# SmartDriveTestStand_SingleCape.net
KiCad netlist of a schematic drawn in EAGLE
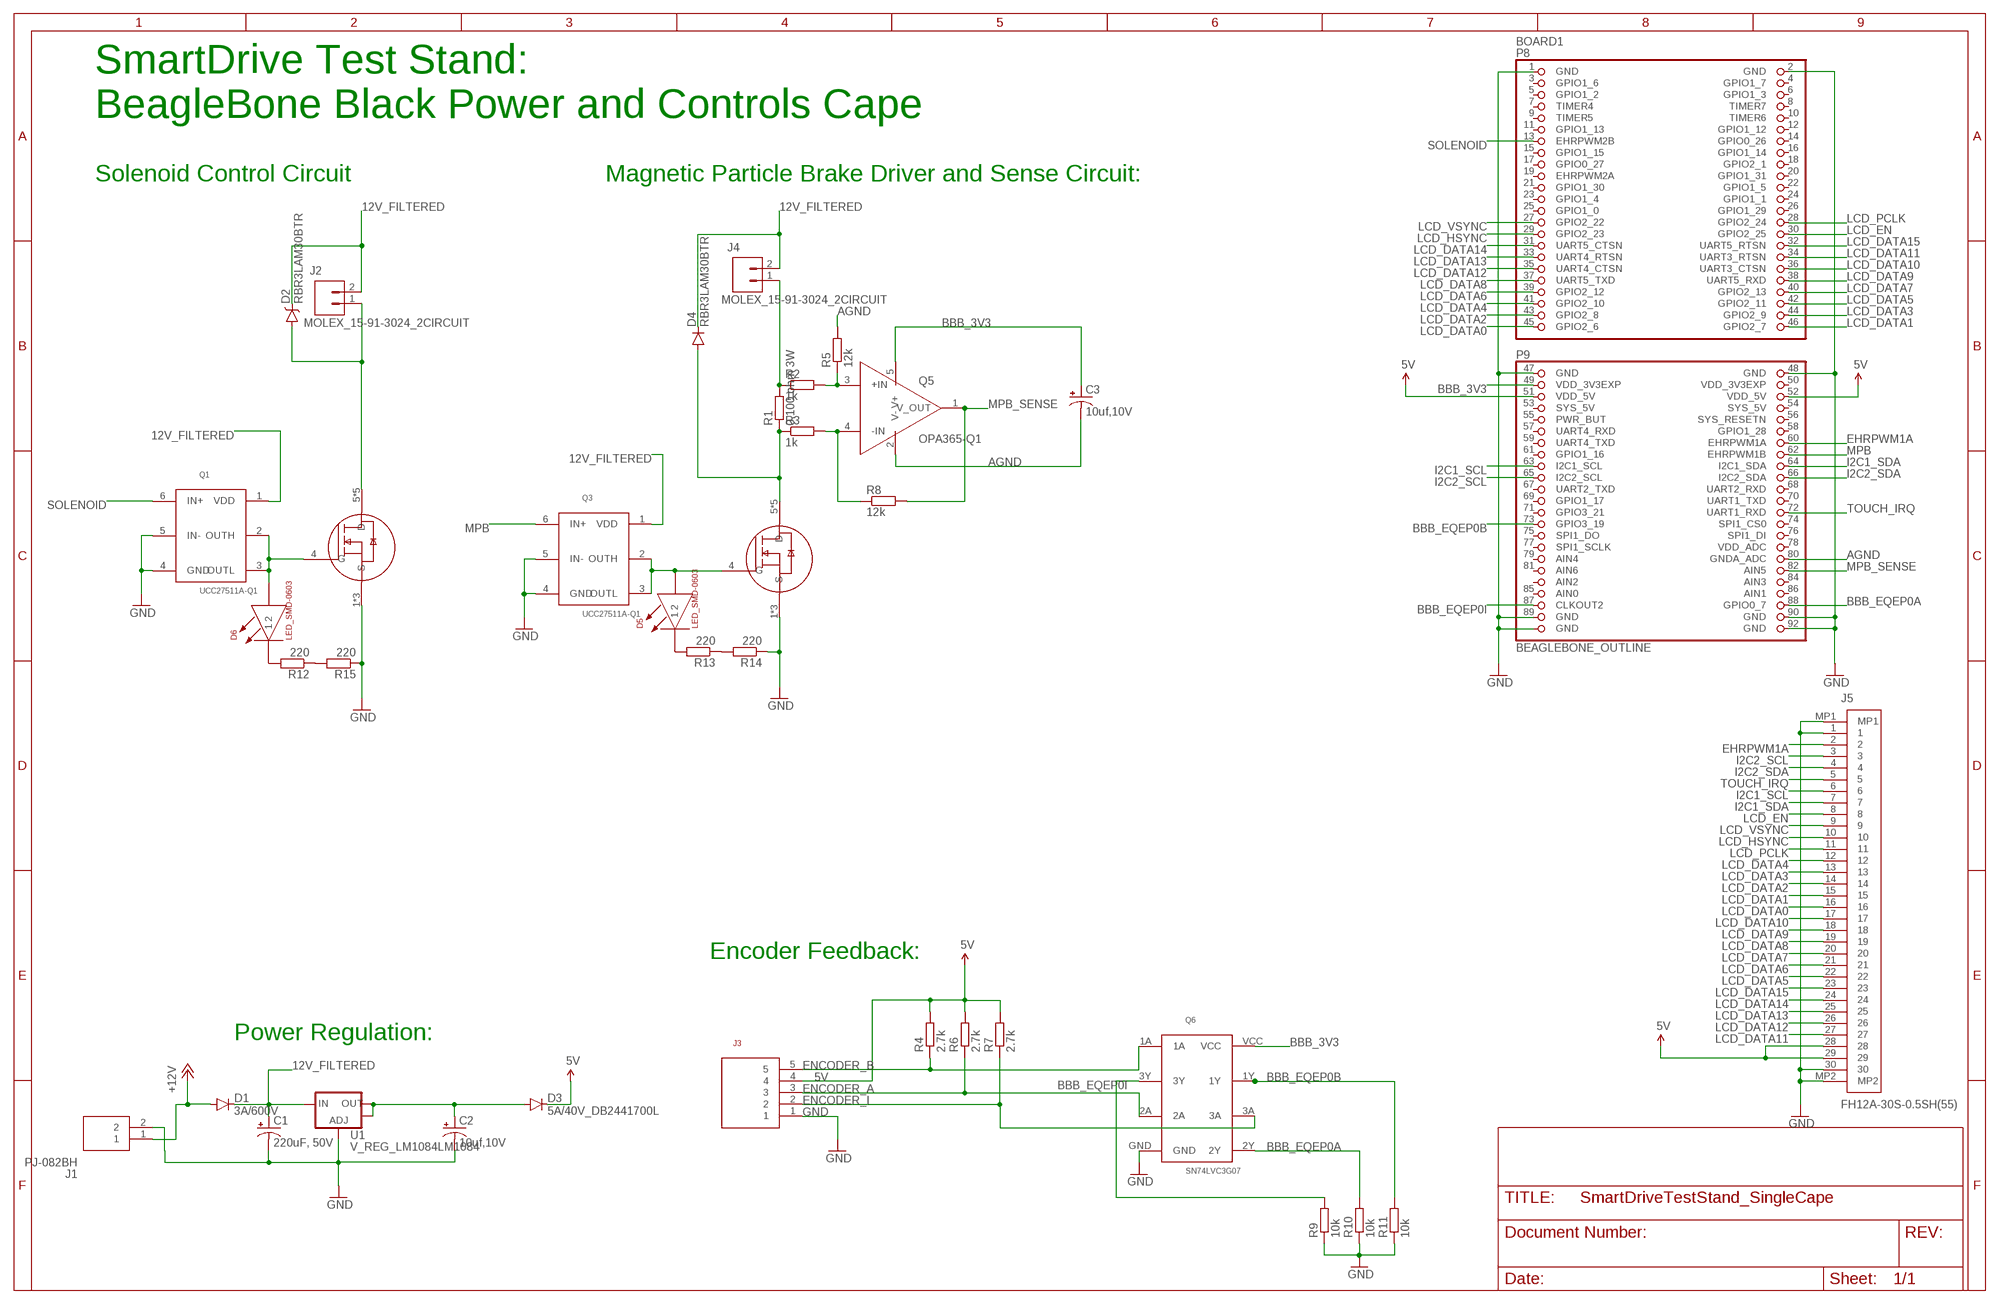
[diagram p0: schematic, sheet 1]

(export (version "E")
  (design (tool "Eeschema 10.0.6"))
  (components
    (comp (ref "BOARD1")
      (value "BEAGLEBONE_OUTLINE")
      (footprint "eagle-import:BEAGLEBONE_SHIELD")
      (libsource (lib "eagle-import") (part "BEAGLEBONE_OUTLINE"))
    )
    (comp (ref "C1")
      (value "220uF, 50V")
      (footprint "eagle-import:PANASONIC_G")
      (libsource (lib "eagle-import") (part "CAP_POLG"))
    )
    (comp (ref "C2")
      (value "10uf,10V")
      (footprint "eagle-import:EIA3216-KIT")
      (libsource (lib "eagle-import") (part "CAP_POL1206-KIT"))
    )
    (comp (ref "C3")
      (value "10uf,10V")
      (footprint "eagle-import:EIA3216-KIT")
      (libsource (lib "eagle-import") (part "CAP_POL1206-KIT"))
    )
    (comp (ref "D1")
      (value "3A/600V")
      (footprint "eagle-import:SMC")
      (libsource (lib "eagle-import") (part "DIODEES3J"))
    )
    (comp (ref "D2")
      (value "RBR3LAM30BTR")
      (footprint "eagle-import:SMA-DIODE")
      (libsource (lib "eagle-import") (part "DIODE-SCHOTTKYRBR3LAM30B"))
    )
    (comp (ref "D3")
      (value "5A/40V_DB2441700L")
      (footprint "eagle-import:SMA-DIODE_ALT")
      (libsource (lib "eagle-import") (part "DIODESMA-ALT"))
    )
    (comp (ref "D4")
      (value "RBR3LAM30BTR")
      (footprint "eagle-import:SMA-DIODE")
      (libsource (lib "eagle-import") (part "DIODESMA"))
    )
    (comp (ref "D5")
      (value "LED_SMD-0603")
      (footprint "eagle-import:0603_LED")
      (libsource (lib "eagle-import") (part "LED_SMD-0603"))
    )
    (comp (ref "D6")
      (value "LED_SMD-0603")
      (footprint "eagle-import:0603_LED")
      (libsource (lib "eagle-import") (part "LED_SMD-0603"))
    )
    (comp (ref "J1")
      (value "PJ-082BH")
      (footprint "eagle-import:PJ-082BH")
      (fields (field (name "MOUSER_PART_NUMBER") "490-PJ-082BH"))
      (libsource (lib "eagle-import") (part "PJ-082BH"))
    )
    (comp (ref "J2")
      (value "MOLEX_15-91-3024_2CIRCUIT")
      (footprint "eagle-import:MOLEX15-91-3024_2CIRCUIT")
      (libsource (lib "eagle-import") (part "MOLEX_15-91-3024_2CIRCUIT"))
    )
    (comp (ref "J3")
      (value "MOLEX_15-91-3053_5CIRCUIT")
      (footprint "eagle-import:MOLEX15-91-3053-5CIRCUIT")
      (libsource (lib "eagle-import") (part "MOLEX_15-91-3053_5CIRCUIT"))
    )
    (comp (ref "J4")
      (value "MOLEX_15-91-3024_2CIRCUIT")
      (footprint "eagle-import:MOLEX15-91-3024_2CIRCUIT")
      (libsource (lib "eagle-import") (part "MOLEX_15-91-3024_2CIRCUIT"))
    )
    (comp (ref "J5")
      (value "FH12A-30S-0.5SH(55)")
      (footprint "eagle-import:FH12A30S05SH55")
      (fields (field (name "RS_PART_NUMBER") "7148083P"))
      (libsource (lib "eagle-import") (part "FH12A-30S-0.5SH(55)"))
    )
    (comp (ref "Q1")
      (value "UCC27511A-Q1")
      (footprint "eagle-import:SOT23-6")
      (libsource (lib "eagle-import") (part "UCC27511A-Q1"))
    )
    (comp (ref "Q2")
      (value "MOSFET_NCHANNELTI_CSD18533Q5A")
      (footprint "eagle-import:SON_5X6MM_NEXFET")
      (libsource (lib "eagle-import") (part "MOSFET_NCHANNELTI_CSD18533Q5A"))
    )
    (comp (ref "Q3")
      (value "UCC27511A-Q1")
      (footprint "eagle-import:SOT23-6")
      (libsource (lib "eagle-import") (part "UCC27511A-Q1"))
    )
    (comp (ref "Q4")
      (value "MOSFET_NCHANNELTI_CSD18533Q5A")
      (footprint "eagle-import:SON_5X6MM_NEXFET")
      (libsource (lib "eagle-import") (part "MOSFET_NCHANNELTI_CSD18533Q5A"))
    )
    (comp (ref "Q5")
      (value "OPA365-Q1")
      (footprint "eagle-import:SOT23-5")
      (libsource (lib "eagle-import") (part "OPA365-Q1"))
    )
    (comp (ref "Q6")
      (value "SN74LVC3G07")
      (footprint "eagle-import:SN74LVC3G07")
      (libsource (lib "eagle-import") (part "SN74LVC3G07"))
    )
    (comp (ref "R1")
      (value "0.100 ohm 3W")
      (footprint "eagle-import:RESISTOR-2512")
      (libsource (lib "eagle-import") (part "RESISTOR-2512"))
    )
    (comp (ref "R2")
      (value "1k")
      (footprint "eagle-import:RESISTOR-0603")
      (libsource (lib "eagle-import") (part "RESISTOR-0603"))
    )
    (comp (ref "R3")
      (value "1k")
      (footprint "eagle-import:RESISTOR-0603")
      (libsource (lib "eagle-import") (part "RESISTOR-0603"))
    )
    (comp (ref "R4")
      (value "2.7k")
      (footprint "eagle-import:RESISTOR-0603")
      (libsource (lib "eagle-import") (part "RESISTOR-0603"))
    )
    (comp (ref "R5")
      (value "12k")
      (footprint "eagle-import:RESISTOR-0603")
      (libsource (lib "eagle-import") (part "RESISTOR-0603"))
    )
    (comp (ref "R6")
      (value "2.7k")
      (footprint "eagle-import:RESISTOR-0603")
      (libsource (lib "eagle-import") (part "RESISTOR-0603"))
    )
    (comp (ref "R7")
      (value "2.7k")
      (footprint "eagle-import:RESISTOR-0603")
      (libsource (lib "eagle-import") (part "RESISTOR-0603"))
    )
    (comp (ref "R8")
      (value "12k")
      (footprint "eagle-import:RESISTOR-0603")
      (libsource (lib "eagle-import") (part "RESISTOR-0603"))
    )
    (comp (ref "R9")
      (value "10k")
      (footprint "eagle-import:RESISTOR-0603")
      (libsource (lib "eagle-import") (part "RESISTOR-0603"))
    )
    (comp (ref "R10")
      (value "10k")
      (footprint "eagle-import:RESISTOR-0603")
      (libsource (lib "eagle-import") (part "RESISTOR-0603"))
    )
    (comp (ref "R11")
      (value "10k")
      (footprint "eagle-import:RESISTOR-0603")
      (libsource (lib "eagle-import") (part "RESISTOR-0603"))
    )
    (comp (ref "R12")
      (value "220")
      (footprint "eagle-import:RESISTOR-0603")
      (libsource (lib "eagle-import") (part "RESISTOR-0603"))
    )
    (comp (ref "R13")
      (value "220")
      (footprint "eagle-import:RESISTOR-0603")
      (libsource (lib "eagle-import") (part "RESISTOR-0603"))
    )
    (comp (ref "R14")
      (value "220")
      (footprint "eagle-import:RESISTOR-0603")
      (libsource (lib "eagle-import") (part "RESISTOR-0603"))
    )
    (comp (ref "R15")
      (value "220")
      (footprint "eagle-import:RESISTOR-0603")
      (libsource (lib "eagle-import") (part "RESISTOR-0603"))
    )
    (comp (ref "U1")
      (value "V_REG_LM1084LM1084")
      (footprint "eagle-import:TO-263-3")
      (libsource (lib "eagle-import") (part "V_REG_LM1084LM1084"))
    )
  )
  (nets
    (net (code "1") (name "+12V") (class "Default")
      (node (ref "D1") (pin "A") (pinfunction "A_A") (pintype "passive"))
      (node (ref "J1") (pin "1") (pinfunction "1_1") (pintype "bidirectional"))
    )
    (net (code "2") (name "/12V_FILTERED") (class "Default")
      (node (ref "C1") (pin "+") (pinfunction "+_+") (pintype "passive"))
      (node (ref "D1") (pin "C") (pinfunction "C_C") (pintype "passive"))
      (node (ref "D2") (pin "C") (pinfunction "C_C") (pintype "passive"))
      (node (ref "D4") (pin "C") (pinfunction "C_C") (pintype "passive"))
      (node (ref "J2") (pin "2") (pinfunction "2_2") (pintype "passive"))
      (node (ref "J4") (pin "2") (pinfunction "2_2") (pintype "passive"))
      (node (ref "Q1") (pin "1") (pinfunction "VDD_1") (pintype "bidirectional"))
      (node (ref "Q3") (pin "1") (pinfunction "VDD_1") (pintype "bidirectional"))
      (node (ref "U1") (pin "3") (pinfunction "IN_3") (pintype "input"))
    )
    (net (code "3") (name "/AGND") (class "Default")
      (node (ref "BOARD1") (pin "80") (pinfunction "GNDA_ADC_80") (pintype "passive"))
      (node (ref "C3") (pin "C") (pinfunction "-_C") (pintype "passive"))
      (node (ref "Q5") (pin "2") (pinfunction "V-_2") (pintype "power_in"))
      (node (ref "R5") (pin "P$2") (pinfunction "2_P$2") (pintype "passive"))
    )
    (net (code "4") (name "/AIN0") (class "Default")
      (node (ref "BOARD1") (pin "85") (pinfunction "AIN0_85") (pintype "power_in"))
    )
    (net (code "5") (name "/BBB_3V3") (class "Default")
      (node (ref "BOARD1") (pin "49") (pinfunction "VDD_3V3EXP_49") (pintype "power_in"))
      (node (ref "C3") (pin "A") (pinfunction "+_A") (pintype "passive"))
      (node (ref "Q5") (pin "5") (pinfunction "V+_5") (pintype "power_in"))
      (node (ref "Q6") (pin "VCC") (pinfunction "VCC_VCC") (pintype "bidirectional"))
    )
    (net (code "6") (name "/BBB_EQEP0A") (class "Default")
      (node (ref "BOARD1") (pin "88") (pinfunction "GPIO0_7_88") (pintype "passive"))
      (node (ref "Q6") (pin "2Y") (pinfunction "2Y_2Y") (pintype "bidirectional"))
      (node (ref "R10") (pin "P$2") (pinfunction "2_P$2") (pintype "passive"))
    )
    (net (code "7") (name "/BBB_EQEP0B") (class "Default")
      (node (ref "BOARD1") (pin "73") (pinfunction "GPIO3_19_73") (pintype "passive"))
      (node (ref "Q6") (pin "1Y") (pinfunction "1Y_1Y") (pintype "bidirectional"))
      (node (ref "R11") (pin "P$2") (pinfunction "2_P$2") (pintype "passive"))
    )
    (net (code "8") (name "/BBB_EQEP0I") (class "Default")
      (node (ref "BOARD1") (pin "87") (pinfunction "CLKOUT2_87") (pintype "input"))
      (node (ref "Q6") (pin "3Y") (pinfunction "3Y_3Y") (pintype "bidirectional"))
      (node (ref "R9") (pin "P$2") (pinfunction "2_P$2") (pintype "passive"))
    )
    (net (code "9") (name "/EHRPWM1A") (class "Default")
      (node (ref "BOARD1") (pin "60") (pinfunction "EHRPWM1A_60") (pintype "passive"))
      (node (ref "J5") (pin "2") (pinfunction "2_2") (pintype "bidirectional"))
    )
    (net (code "10") (name "/ENCODER_A") (class "Default")
      (node (ref "J3") (pin "3") (pinfunction "3_3") (pintype "passive"))
      (node (ref "Q6") (pin "2A") (pinfunction "2A_2A") (pintype "bidirectional"))
      (node (ref "R6") (pin "P$1") (pinfunction "1_P$1") (pintype "passive"))
    )
    (net (code "11") (name "/ENCODER_B") (class "Default")
      (node (ref "J3") (pin "5") (pinfunction "5_5") (pintype "passive"))
      (node (ref "Q6") (pin "1A") (pinfunction "1A_1A") (pintype "bidirectional"))
      (node (ref "R4") (pin "P$1") (pinfunction "1_P$1") (pintype "passive"))
    )
    (net (code "12") (name "/ENCODER_I") (class "Default")
      (node (ref "J3") (pin "2") (pinfunction "2_2") (pintype "passive"))
      (node (ref "Q6") (pin "3A") (pinfunction "3A_3A") (pintype "bidirectional"))
      (node (ref "R7") (pin "P$1") (pinfunction "1_P$1") (pintype "passive"))
    )
    (net (code "13") (name "/I2C1_SCL") (class "Default")
      (node (ref "BOARD1") (pin "63") (pinfunction "I2C1_SCL_63") (pintype "passive"))
      (node (ref "J5") (pin "6") (pinfunction "6_6") (pintype "bidirectional"))
    )
    (net (code "14") (name "/I2C1_SDA") (class "Default")
      (node (ref "BOARD1") (pin "64") (pinfunction "I2C1_SDA_64") (pintype "passive"))
      (node (ref "J5") (pin "7") (pinfunction "7_7") (pintype "bidirectional"))
    )
    (net (code "15") (name "/I2C2_SCL") (class "Default")
      (node (ref "BOARD1") (pin "65") (pinfunction "I2C2_SCL_65") (pintype "passive"))
      (node (ref "J5") (pin "3") (pinfunction "3_3") (pintype "bidirectional"))
    )
    (net (code "16") (name "/I2C2_SDA") (class "Default")
      (node (ref "BOARD1") (pin "66") (pinfunction "I2C2_SDA_66") (pintype "passive"))
      (node (ref "J5") (pin "4") (pinfunction "4_4") (pintype "bidirectional"))
    )
    (net (code "17") (name "/LCD_DATA0") (class "Default")
      (node (ref "BOARD1") (pin "45") (pinfunction "GPIO2_6_45") (pintype "passive"))
      (node (ref "J5") (pin "16") (pinfunction "16_16") (pintype "bidirectional"))
    )
    (net (code "18") (name "/LCD_DATA1") (class "Default")
      (node (ref "BOARD1") (pin "46") (pinfunction "GPIO2_7_46") (pintype "passive"))
      (node (ref "J5") (pin "15") (pinfunction "15_15") (pintype "bidirectional"))
    )
    (net (code "19") (name "/LCD_DATA2") (class "Default")
      (node (ref "BOARD1") (pin "43") (pinfunction "GPIO2_8_43") (pintype "passive"))
      (node (ref "J5") (pin "14") (pinfunction "14_14") (pintype "bidirectional"))
    )
    (net (code "20") (name "/LCD_DATA3") (class "Default")
      (node (ref "BOARD1") (pin "44") (pinfunction "GPIO2_9_44") (pintype "passive"))
      (node (ref "J5") (pin "13") (pinfunction "13_13") (pintype "bidirectional"))
    )
    (net (code "21") (name "/LCD_DATA4") (class "Default")
      (node (ref "BOARD1") (pin "41") (pinfunction "GPIO2_10_41") (pintype "passive"))
      (node (ref "J5") (pin "12") (pinfunction "12_12") (pintype "bidirectional"))
    )
    (net (code "22") (name "/LCD_DATA5") (class "Default")
      (node (ref "BOARD1") (pin "42") (pinfunction "GPIO2_11_42") (pintype "passive"))
      (node (ref "J5") (pin "22") (pinfunction "22_22") (pintype "bidirectional"))
    )
    (net (code "23") (name "/LCD_DATA6") (class "Default")
      (node (ref "BOARD1") (pin "39") (pinfunction "GPIO2_12_39") (pintype "passive"))
      (node (ref "J5") (pin "21") (pinfunction "21_21") (pintype "bidirectional"))
    )
    (net (code "24") (name "/LCD_DATA7") (class "Default")
      (node (ref "BOARD1") (pin "40") (pinfunction "GPIO2_13_40") (pintype "passive"))
      (node (ref "J5") (pin "20") (pinfunction "20_20") (pintype "bidirectional"))
    )
    (net (code "25") (name "/LCD_DATA8") (class "Default")
      (node (ref "BOARD1") (pin "37") (pinfunction "UART5_TXD_37") (pintype "passive"))
      (node (ref "J5") (pin "19") (pinfunction "19_19") (pintype "bidirectional"))
    )
    (net (code "26") (name "/LCD_DATA9") (class "Default")
      (node (ref "BOARD1") (pin "38") (pinfunction "UART5_RXD_38") (pintype "passive"))
      (node (ref "J5") (pin "18") (pinfunction "18_18") (pintype "bidirectional"))
    )
    (net (code "27") (name "/LCD_DATA10") (class "Default")
      (node (ref "BOARD1") (pin "36") (pinfunction "UART3_CTSN_36") (pintype "passive"))
      (node (ref "J5") (pin "17") (pinfunction "17_17") (pintype "bidirectional"))
    )
    (net (code "28") (name "/LCD_DATA11") (class "Default")
      (node (ref "BOARD1") (pin "34") (pinfunction "UART3_RTSN_34") (pintype "passive"))
      (node (ref "J5") (pin "27") (pinfunction "27_27") (pintype "bidirectional"))
    )
    (net (code "29") (name "/LCD_DATA12") (class "Default")
      (node (ref "BOARD1") (pin "35") (pinfunction "UART4_CTSN_35") (pintype "passive"))
      (node (ref "J5") (pin "26") (pinfunction "26_26") (pintype "bidirectional"))
    )
    (net (code "30") (name "/LCD_DATA13") (class "Default")
      (node (ref "BOARD1") (pin "33") (pinfunction "UART4_RTSN_33") (pintype "passive"))
      (node (ref "J5") (pin "25") (pinfunction "25_25") (pintype "bidirectional"))
    )
    (net (code "31") (name "/LCD_DATA14") (class "Default")
      (node (ref "BOARD1") (pin "31") (pinfunction "UART5_CTSN_31") (pintype "passive"))
      (node (ref "J5") (pin "24") (pinfunction "24_24") (pintype "bidirectional"))
    )
    (net (code "32") (name "/LCD_DATA15") (class "Default")
      (node (ref "BOARD1") (pin "32") (pinfunction "UART5_RTSN_32") (pintype "passive"))
      (node (ref "J5") (pin "23") (pinfunction "23_23") (pintype "bidirectional"))
    )
    (net (code "33") (name "/LCD_EN") (class "Default")
      (node (ref "BOARD1") (pin "30") (pinfunction "GPIO2_25_30") (pintype "passive"))
      (node (ref "J5") (pin "8") (pinfunction "8_8") (pintype "bidirectional"))
    )
    (net (code "34") (name "/LCD_HSYNC") (class "Default")
      (node (ref "BOARD1") (pin "29") (pinfunction "GPIO2_23_29") (pintype "passive"))
      (node (ref "J5") (pin "10") (pinfunction "10_10") (pintype "bidirectional"))
    )
    (net (code "35") (name "/LCD_PCLK") (class "Default")
      (node (ref "BOARD1") (pin "28") (pinfunction "GPIO2_24_28") (pintype "passive"))
      (node (ref "J5") (pin "11") (pinfunction "11_11") (pintype "bidirectional"))
    )
    (net (code "36") (name "/LCD_VSYNC") (class "Default")
      (node (ref "BOARD1") (pin "27") (pinfunction "GPIO2_22_27") (pintype "passive"))
      (node (ref "J5") (pin "9") (pinfunction "9_9") (pintype "bidirectional"))
    )
    (net (code "37") (name "/MPB") (class "Default")
      (node (ref "BOARD1") (pin "62") (pinfunction "EHRPWM1B_62") (pintype "passive"))
      (node (ref "Q3") (pin "6") (pinfunction "IN+_6") (pintype "bidirectional"))
    )
    (net (code "38") (name "/MPB_SENSE") (class "Default")
      (node (ref "BOARD1") (pin "82") (pinfunction "AIN5_82") (pintype "passive"))
      (node (ref "Q5") (pin "1") (pinfunction "V_OUT_1") (pintype "output"))
      (node (ref "R8") (pin "P$2") (pinfunction "2_P$2") (pintype "passive"))
    )
    (net (code "39") (name "/SOLENOID") (class "Default")
      (node (ref "BOARD1") (pin "13") (pinfunction "EHRPWM2B_13") (pintype "passive"))
      (node (ref "Q1") (pin "6") (pinfunction "IN+_6") (pintype "bidirectional"))
    )
    (net (code "40") (name "/SYS_5V") (class "Default")
      (node (ref "BOARD1") (pin "53") (pinfunction "SYS_5V_53") (pintype "power_in"))
    )
    (net (code "41") (name "/TOUCH_IRQ") (class "Default")
      (node (ref "BOARD1") (pin "72") (pinfunction "UART1_RXD_72") (pintype "passive"))
      (node (ref "J5") (pin "5") (pinfunction "5_5") (pintype "bidirectional"))
    )
    (net (code "42") (name "/VDD_3V3EXP") (class "Default")
      (node (ref "BOARD1") (pin "50") (pinfunction "VDD_3V3EXP_50") (pintype "power_in"))
    )
    (net (code "43") (name "5V") (class "Default")
      (node (ref "BOARD1") (pin "51") (pinfunction "VDD_5V_51") (pintype "power_in"))
      (node (ref "BOARD1") (pin "52") (pinfunction "VDD_5V_52") (pintype "power_in"))
      (node (ref "D3") (pin "C") (pinfunction "C_C") (pintype "passive"))
      (node (ref "J3") (pin "4") (pinfunction "4_4") (pintype "passive"))
      (node (ref "J5") (pin "28") (pinfunction "28_28") (pintype "bidirectional"))
      (node (ref "J5") (pin "29") (pinfunction "29_29") (pintype "bidirectional"))
      (node (ref "R4") (pin "P$2") (pinfunction "2_P$2") (pintype "passive"))
      (node (ref "R6") (pin "P$2") (pinfunction "2_P$2") (pintype "passive"))
      (node (ref "R7") (pin "P$2") (pinfunction "2_P$2") (pintype "passive"))
    )
    (net (code "44") (name "GND") (class "Default")
      (node (ref "BOARD1") (pin "1") (pinfunction "GND_1") (pintype "power_in"))
      (node (ref "BOARD1") (pin "2") (pinfunction "GND_2") (pintype "power_in"))
      (node (ref "BOARD1") (pin "47") (pinfunction "GND_47") (pintype "power_in"))
      (node (ref "BOARD1") (pin "48") (pinfunction "GND_48") (pintype "power_in"))
      (node (ref "BOARD1") (pin "89") (pinfunction "GND_89") (pintype "power_in"))
      (node (ref "BOARD1") (pin "90") (pinfunction "GND_90") (pintype "power_in"))
      (node (ref "BOARD1") (pin "91") (pinfunction "GND_91") (pintype "power_in"))
      (node (ref "BOARD1") (pin "92") (pinfunction "GND_92") (pintype "power_in"))
      (node (ref "C1") (pin "-") (pinfunction "-_-") (pintype "passive"))
      (node (ref "C2") (pin "C") (pinfunction "-_C") (pintype "passive"))
      (node (ref "J1") (pin "2") (pinfunction "2_2") (pintype "bidirectional"))
      (node (ref "J3") (pin "1") (pinfunction "1_1") (pintype "passive"))
      (node (ref "J5") (pin "1") (pinfunction "1_1") (pintype "bidirectional"))
      (node (ref "J5") (pin "30") (pinfunction "30_30") (pintype "bidirectional"))
      (node (ref "J5") (pin "MP1") (pinfunction "MP1_MP1") (pintype "bidirectional"))
      (node (ref "J5") (pin "MP2") (pinfunction "MP2_MP2") (pintype "bidirectional"))
      (node (ref "Q1") (pin "4") (pinfunction "GND_4") (pintype "bidirectional"))
      (node (ref "Q1") (pin "5") (pinfunction "IN-_5") (pintype "bidirectional"))
      (node (ref "Q2") (pin "1") (pinfunction "S_1") (pintype "power_in"))
      (node (ref "Q2") (pin "2") (pinfunction "S_2") (pintype "power_in"))
      (node (ref "Q2") (pin "3") (pinfunction "S_3") (pintype "power_in"))
      (node (ref "Q3") (pin "4") (pinfunction "GND_4") (pintype "bidirectional"))
      (node (ref "Q3") (pin "5") (pinfunction "IN-_5") (pintype "bidirectional"))
      (node (ref "Q4") (pin "1") (pinfunction "S_1") (pintype "power_in"))
      (node (ref "Q4") (pin "2") (pinfunction "S_2") (pintype "power_in"))
      (node (ref "Q4") (pin "3") (pinfunction "S_3") (pintype "power_in"))
      (node (ref "Q6") (pin "GND") (pinfunction "GND_GND") (pintype "bidirectional"))
      (node (ref "R10") (pin "P$1") (pinfunction "1_P$1") (pintype "passive"))
      (node (ref "R11") (pin "P$1") (pinfunction "1_P$1") (pintype "passive"))
      (node (ref "R14") (pin "P$1") (pinfunction "1_P$1") (pintype "passive"))
      (node (ref "R15") (pin "P$1") (pinfunction "1_P$1") (pintype "passive"))
      (node (ref "R9") (pin "P$1") (pinfunction "1_P$1") (pintype "passive"))
      (node (ref "U1") (pin "1") (pinfunction "ADJ_1") (pintype "input"))
    )
    (net (code "45") (name "Net-(C2-+)") (class "Default")
      (node (ref "C2") (pin "A") (pinfunction "+_A") (pintype "passive"))
      (node (ref "D3") (pin "A") (pinfunction "A_A") (pintype "passive"))
      (node (ref "U1") (pin "2") (pinfunction "OUT_2") (pintype "output"))
      (node (ref "U1") (pin "4") (pinfunction "OUT_4") (pintype "output"))
    )
    (net (code "46") (name "Net-(D2-PadA)") (class "Default")
      (node (ref "D2") (pin "A") (pinfunction "A_A") (pintype "passive"))
      (node (ref "J2") (pin "1") (pinfunction "1_1") (pintype "passive"))
      (node (ref "Q2") (pin "5") (pinfunction "D_5") (pintype "power_in"))
      (node (ref "Q2") (pin "6") (pinfunction "D_6") (pintype "power_in"))
      (node (ref "Q2") (pin "7") (pinfunction "D_7") (pintype "power_in"))
      (node (ref "Q2") (pin "8") (pinfunction "D_8") (pintype "power_in"))
      (node (ref "Q2") (pin "PAD") (pinfunction "D_PAD") (pintype "power_in"))
    )
    (net (code "47") (name "Net-(D5-1)") (class "Default")
      (node (ref "D5") (pin "C") (pinfunction "1_C") (pintype "output"))
      (node (ref "R13") (pin "P$2") (pinfunction "2_P$2") (pintype "passive"))
    )
    (net (code "48") (name "Net-(D5-2)") (class "Default")
      (node (ref "D5") (pin "A") (pinfunction "2_A") (pintype "input"))
      (node (ref "Q3") (pin "2") (pinfunction "OUTH_2") (pintype "bidirectional"))
      (node (ref "Q3") (pin "3") (pinfunction "OUTL_3") (pintype "bidirectional"))
      (node (ref "Q4") (pin "4") (pinfunction "G_4") (pintype "input"))
    )
    (net (code "49") (name "Net-(D6-1)") (class "Default")
      (node (ref "D6") (pin "C") (pinfunction "1_C") (pintype "output"))
      (node (ref "R12") (pin "P$2") (pinfunction "2_P$2") (pintype "passive"))
    )
    (net (code "50") (name "Net-(D6-2)") (class "Default")
      (node (ref "D6") (pin "A") (pinfunction "2_A") (pintype "input"))
      (node (ref "Q1") (pin "2") (pinfunction "OUTH_2") (pintype "bidirectional"))
      (node (ref "Q1") (pin "3") (pinfunction "OUTL_3") (pintype "bidirectional"))
      (node (ref "Q2") (pin "4") (pinfunction "G_4") (pintype "input"))
    )
    (net (code "51") (name "Net-(Q5-+IN)") (class "Default")
      (node (ref "Q5") (pin "3") (pinfunction "+IN_3") (pintype "input"))
      (node (ref "R2") (pin "P$2") (pinfunction "2_P$2") (pintype "passive"))
      (node (ref "R5") (pin "P$1") (pinfunction "1_P$1") (pintype "passive"))
    )
    (net (code "52") (name "Net-(Q5--IN)") (class "Default")
      (node (ref "Q5") (pin "4") (pinfunction "-IN_4") (pintype "input"))
      (node (ref "R3") (pin "P$2") (pinfunction "2_P$2") (pintype "passive"))
      (node (ref "R8") (pin "P$1") (pinfunction "1_P$1") (pintype "passive"))
    )
    (net (code "53") (name "Net-(R2-1)") (class "Default")
      (node (ref "J4") (pin "1") (pinfunction "1_1") (pintype "passive"))
      (node (ref "R1") (pin "2") (pinfunction "2_2") (pintype "passive"))
      (node (ref "R2") (pin "P$1") (pinfunction "1_P$1") (pintype "passive"))
    )
    (net (code "54") (name "Net-(R3-1)") (class "Default")
      (node (ref "D4") (pin "A") (pinfunction "A_A") (pintype "passive"))
      (node (ref "Q4") (pin "5") (pinfunction "D_5") (pintype "power_in"))
      (node (ref "Q4") (pin "6") (pinfunction "D_6") (pintype "power_in"))
      (node (ref "Q4") (pin "7") (pinfunction "D_7") (pintype "power_in"))
      (node (ref "Q4") (pin "8") (pinfunction "D_8") (pintype "power_in"))
      (node (ref "Q4") (pin "PAD") (pinfunction "D_PAD") (pintype "power_in"))
      (node (ref "R1") (pin "1") (pinfunction "1_1") (pintype "passive"))
      (node (ref "R3") (pin "P$1") (pinfunction "1_P$1") (pintype "passive"))
    )
    (net (code "55") (name "Net-(R12-1)") (class "Default")
      (node (ref "R12") (pin "P$1") (pinfunction "1_P$1") (pintype "passive"))
      (node (ref "R15") (pin "P$2") (pinfunction "2_P$2") (pintype "passive"))
    )
    (net (code "56") (name "Net-(R13-1)") (class "Default")
      (node (ref "R13") (pin "P$1") (pinfunction "1_P$1") (pintype "passive"))
      (node (ref "R14") (pin "P$2") (pinfunction "2_P$2") (pintype "passive"))
    )
    (net (code "57") (name "unconnected-(BOARD1-AIN1-Pad86)") (class "Default")
      (node (ref "BOARD1") (pin "86") (pinfunction "AIN1_86") (pintype "passive"))
    )
    (net (code "58") (name "unconnected-(BOARD1-AIN2-Pad83)") (class "Default")
      (node (ref "BOARD1") (pin "83") (pinfunction "AIN2_83") (pintype "passive"))
    )
    (net (code "59") (name "unconnected-(BOARD1-AIN3-Pad84)") (class "Default")
      (node (ref "BOARD1") (pin "84") (pinfunction "AIN3_84") (pintype "passive"))
    )
    (net (code "60") (name "unconnected-(BOARD1-AIN4-Pad79)") (class "Default")
      (node (ref "BOARD1") (pin "79") (pinfunction "AIN4_79") (pintype "passive"))
    )
    (net (code "61") (name "unconnected-(BOARD1-AIN6-Pad81)") (class "Default")
      (node (ref "BOARD1") (pin "81") (pinfunction "AIN6_81") (pintype "passive"))
    )
    (net (code "62") (name "unconnected-(BOARD1-EHRPWM2A-Pad19)") (class "Default")
      (node (ref "BOARD1") (pin "19") (pinfunction "EHRPWM2A_19") (pintype "passive"))
    )
    (net (code "63") (name "unconnected-(BOARD1-GPIO0_26-Pad14)") (class "Default")
      (node (ref "BOARD1") (pin "14") (pinfunction "GPIO0_26_14") (pintype "passive"))
    )
    (net (code "64") (name "unconnected-(BOARD1-GPIO0_27-Pad17)") (class "Default")
      (node (ref "BOARD1") (pin "17") (pinfunction "GPIO0_27_17") (pintype "passive"))
    )
    (net (code "65") (name "unconnected-(BOARD1-GPIO1_0-Pad25)") (class "Default")
      (node (ref "BOARD1") (pin "25") (pinfunction "GPIO1_0_25") (pintype "passive"))
    )
    (net (code "66") (name "unconnected-(BOARD1-GPIO1_1-Pad24)") (class "Default")
      (node (ref "BOARD1") (pin "24") (pinfunction "GPIO1_1_24") (pintype "passive"))
    )
    (net (code "67") (name "unconnected-(BOARD1-GPIO1_2-Pad5)") (class "Default")
      (node (ref "BOARD1") (pin "5") (pinfunction "GPIO1_2_5") (pintype "passive"))
    )
    (net (code "68") (name "unconnected-(BOARD1-GPIO1_3-Pad6)") (class "Default")
      (node (ref "BOARD1") (pin "6") (pinfunction "GPIO1_3_6") (pintype "passive"))
    )
    (net (code "69") (name "unconnected-(BOARD1-GPIO1_4-Pad23)") (class "Default")
      (node (ref "BOARD1") (pin "23") (pinfunction "GPIO1_4_23") (pintype "passive"))
    )
    (net (code "70") (name "unconnected-(BOARD1-GPIO1_5-Pad22)") (class "Default")
      (node (ref "BOARD1") (pin "22") (pinfunction "GPIO1_5_22") (pintype "passive"))
    )
    (net (code "71") (name "unconnected-(BOARD1-GPIO1_6-Pad3)") (class "Default")
      (node (ref "BOARD1") (pin "3") (pinfunction "GPIO1_6_3") (pintype "passive"))
    )
    (net (code "72") (name "unconnected-(BOARD1-GPIO1_7-Pad4)") (class "Default")
      (node (ref "BOARD1") (pin "4") (pinfunction "GPIO1_7_4") (pintype "passive"))
    )
    (net (code "73") (name "unconnected-(BOARD1-GPIO1_12-Pad12)") (class "Default")
      (node (ref "BOARD1") (pin "12") (pinfunction "GPIO1_12_12") (pintype "passive"))
    )
    (net (code "74") (name "unconnected-(BOARD1-GPIO1_13-Pad11)") (class "Default")
      (node (ref "BOARD1") (pin "11") (pinfunction "GPIO1_13_11") (pintype "passive"))
    )
    (net (code "75") (name "unconnected-(BOARD1-GPIO1_14-Pad16)") (class "Default")
      (node (ref "BOARD1") (pin "16") (pinfunction "GPIO1_14_16") (pintype "passive"))
    )
    (net (code "76") (name "unconnected-(BOARD1-GPIO1_15-Pad15)") (class "Default")
      (node (ref "BOARD1") (pin "15") (pinfunction "GPIO1_15_15") (pintype "passive"))
    )
    (net (code "77") (name "unconnected-(BOARD1-GPIO1_16-Pad61)") (class "Default")
      (node (ref "BOARD1") (pin "61") (pinfunction "GPIO1_16_61") (pintype "passive"))
    )
    (net (code "78") (name "unconnected-(BOARD1-GPIO1_17-Pad69)") (class "Default")
      (node (ref "BOARD1") (pin "69") (pinfunction "GPIO1_17_69") (pintype "passive"))
    )
    (net (code "79") (name "unconnected-(BOARD1-GPIO1_28-Pad58)") (class "Default")
      (node (ref "BOARD1") (pin "58") (pinfunction "GPIO1_28_58") (pintype "passive"))
    )
    (net (code "80") (name "unconnected-(BOARD1-GPIO1_29-Pad26)") (class "Default")
      (node (ref "BOARD1") (pin "26") (pinfunction "GPIO1_29_26") (pintype "passive"))
    )
    (net (code "81") (name "unconnected-(BOARD1-GPIO1_30-Pad21)") (class "Default")
      (node (ref "BOARD1") (pin "21") (pinfunction "GPIO1_30_21") (pintype "passive"))
    )
    (net (code "82") (name "unconnected-(BOARD1-GPIO1_31-Pad20)") (class "Default")
      (node (ref "BOARD1") (pin "20") (pinfunction "GPIO1_31_20") (pintype "passive"))
    )
    (net (code "83") (name "unconnected-(BOARD1-GPIO2_1-Pad18)") (class "Default")
      (node (ref "BOARD1") (pin "18") (pinfunction "GPIO2_1_18") (pintype "passive"))
    )
    (net (code "84") (name "unconnected-(BOARD1-GPIO3_21-Pad71)") (class "Default")
      (node (ref "BOARD1") (pin "71") (pinfunction "GPIO3_21_71") (pintype "passive"))
    )
    (net (code "85") (name "unconnected-(BOARD1-PWR_BUT-Pad55)") (class "Default")
      (node (ref "BOARD1") (pin "55") (pinfunction "PWR_BUT_55") (pintype "passive"))
    )
    (net (code "86") (name "unconnected-(BOARD1-SPI1_CS0-Pad74)") (class "Default")
      (node (ref "BOARD1") (pin "74") (pinfunction "SPI1_CS0_74") (pintype "passive"))
    )
    (net (code "87") (name "unconnected-(BOARD1-SPI1_DI-Pad76)") (class "Default")
      (node (ref "BOARD1") (pin "76") (pinfunction "SPI1_DI_76") (pintype "passive"))
    )
    (net (code "88") (name "unconnected-(BOARD1-SPI1_DO-Pad75)") (class "Default")
      (node (ref "BOARD1") (pin "75") (pinfunction "SPI1_DO_75") (pintype "passive"))
    )
    (net (code "89") (name "unconnected-(BOARD1-SPI1_SCLK-Pad77)") (class "Default")
      (node (ref "BOARD1") (pin "77") (pinfunction "SPI1_SCLK_77") (pintype "passive"))
    )
    (net (code "90") (name "unconnected-(BOARD1-SYS_5V-Pad54)") (class "Default")
      (node (ref "BOARD1") (pin "54") (pinfunction "SYS_5V_54") (pintype "passive"))
    )
    (net (code "91") (name "unconnected-(BOARD1-SYS_RESETN-Pad56)") (class "Default")
      (node (ref "BOARD1") (pin "56") (pinfunction "SYS_RESETN_56") (pintype "passive"))
    )
    (net (code "92") (name "unconnected-(BOARD1-TIMER4-Pad7)") (class "Default")
      (node (ref "BOARD1") (pin "7") (pinfunction "TIMER4_7") (pintype "passive"))
    )
    (net (code "93") (name "unconnected-(BOARD1-TIMER5-Pad9)") (class "Default")
      (node (ref "BOARD1") (pin "9") (pinfunction "TIMER5_9") (pintype "passive"))
    )
    (net (code "94") (name "unconnected-(BOARD1-TIMER6-Pad10)") (class "Default")
      (node (ref "BOARD1") (pin "10") (pinfunction "TIMER6_10") (pintype "passive"))
    )
    (net (code "95") (name "unconnected-(BOARD1-TIMER7-Pad8)") (class "Default")
      (node (ref "BOARD1") (pin "8") (pinfunction "TIMER7_8") (pintype "passive"))
    )
    (net (code "96") (name "unconnected-(BOARD1-UART1_TXD-Pad70)") (class "Default")
      (node (ref "BOARD1") (pin "70") (pinfunction "UART1_TXD_70") (pintype "passive"))
    )
    (net (code "97") (name "unconnected-(BOARD1-UART2_RXD-Pad68)") (class "Default")
      (node (ref "BOARD1") (pin "68") (pinfunction "UART2_RXD_68") (pintype "passive"))
    )
    (net (code "98") (name "unconnected-(BOARD1-UART2_TXD-Pad67)") (class "Default")
      (node (ref "BOARD1") (pin "67") (pinfunction "UART2_TXD_67") (pintype "passive"))
    )
    (net (code "99") (name "unconnected-(BOARD1-UART4_RXD-Pad57)") (class "Default")
      (node (ref "BOARD1") (pin "57") (pinfunction "UART4_RXD_57") (pintype "passive"))
    )
    (net (code "100") (name "unconnected-(BOARD1-UART4_TXD-Pad59)") (class "Default")
      (node (ref "BOARD1") (pin "59") (pinfunction "UART4_TXD_59") (pintype "passive"))
    )
    (net (code "101") (name "unconnected-(BOARD1-VDD_ADC-Pad78)") (class "Default")
      (node (ref "BOARD1") (pin "78") (pinfunction "VDD_ADC_78") (pintype "passive"))
    )
  )
)
